# Wall_Crawller_Application.net
KiCad netlist of a schematic drawn in Altium Designer
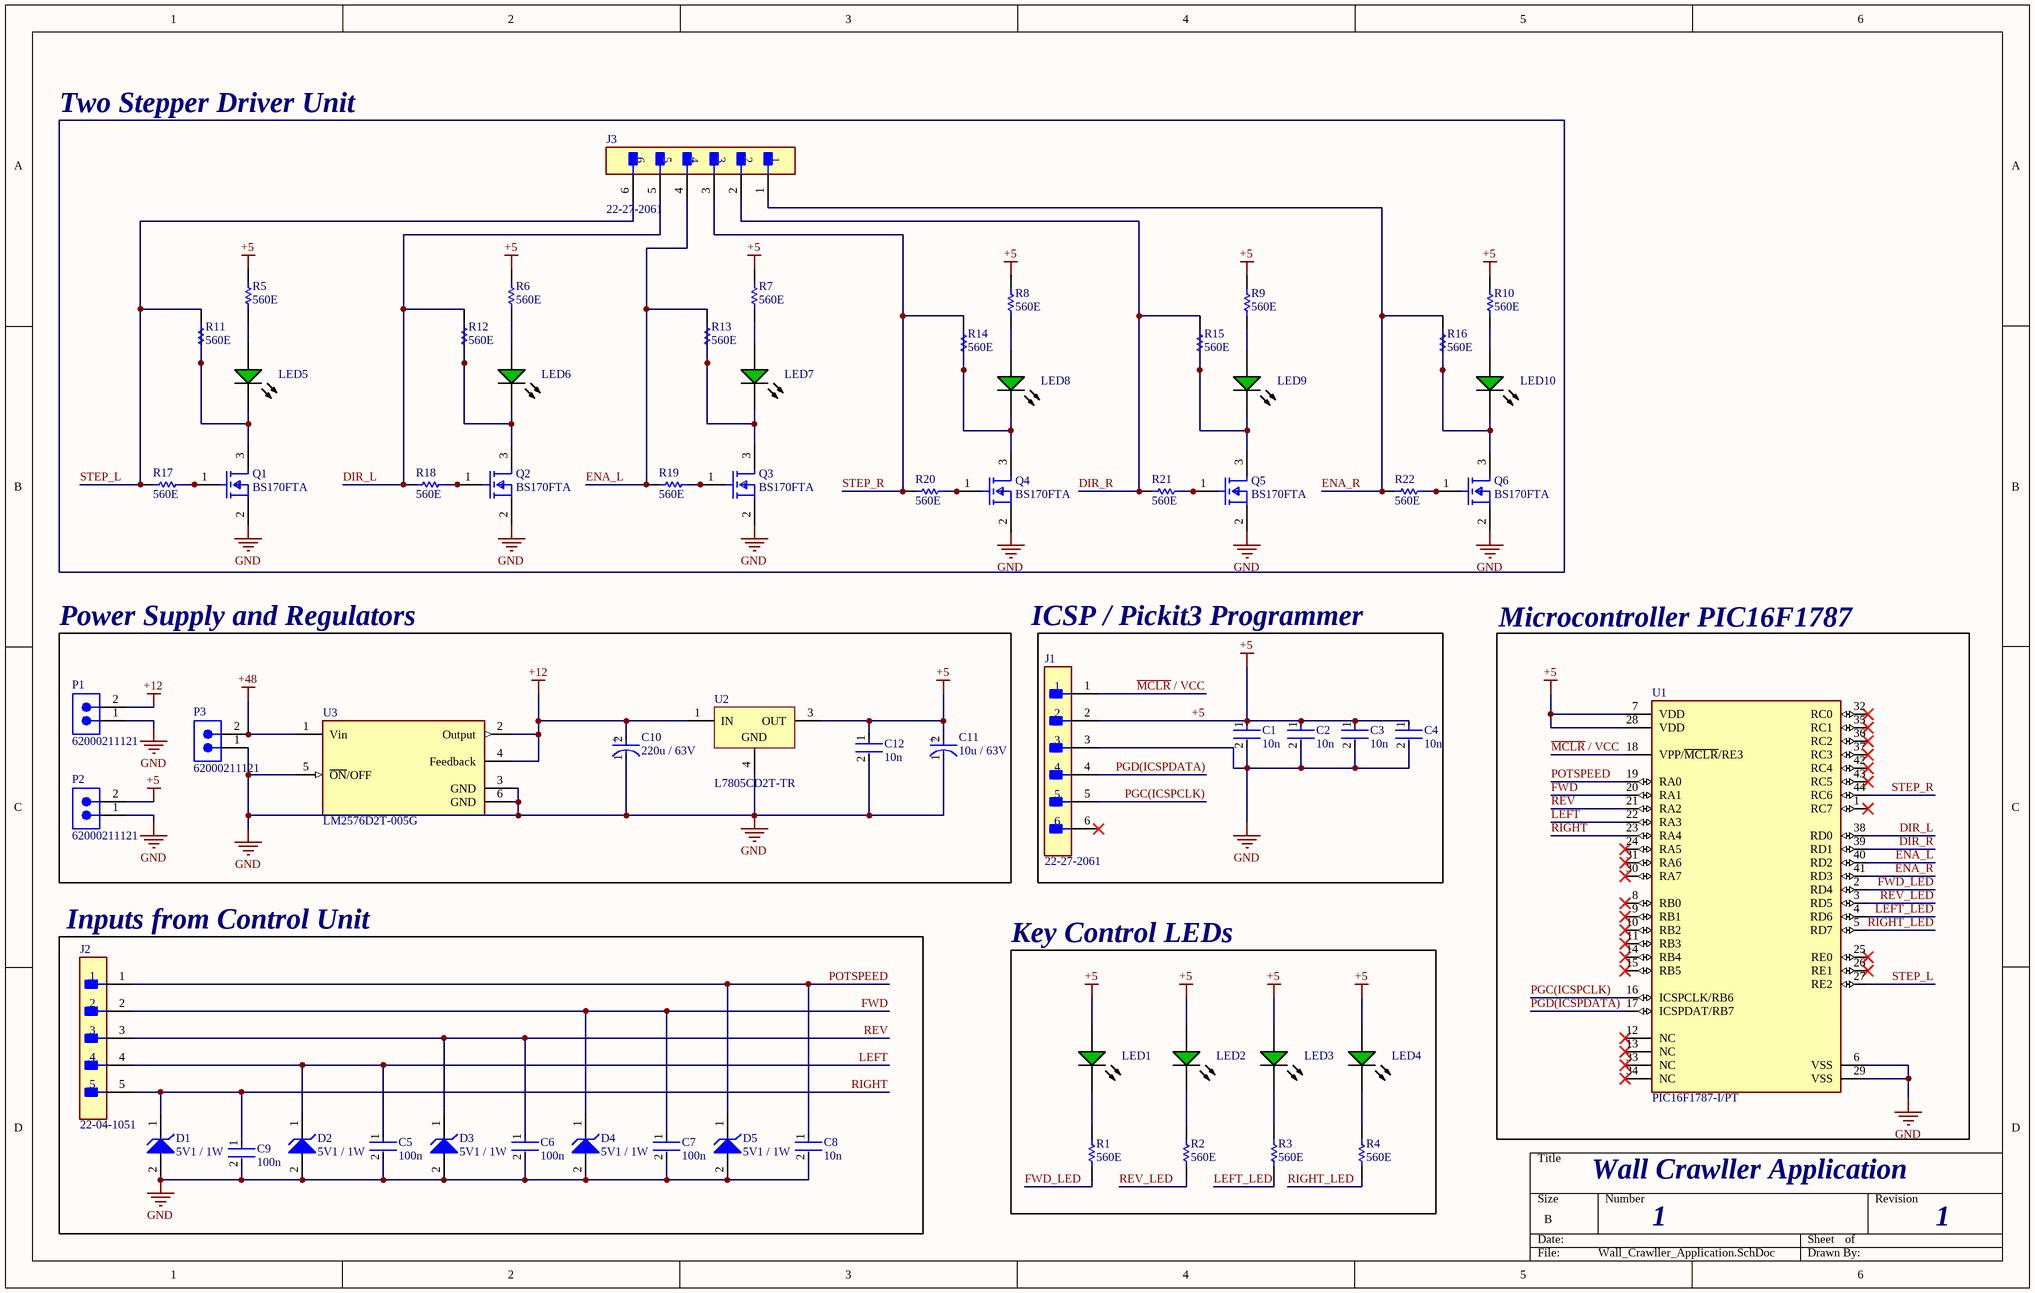
[diagram p0: Wall_Crawller_Application.SchDoc]

(export (version "E")
  (design (tool "Eeschema 10.0.6"))
  (components
    (comp (ref "C1")
      (value "10n")
      (footprint "FP-C0805C-DN-MFG")
      (description "CAP CER 10nF 50V X7R 0805")
      (fields
        (field (name "MANUFACTURER") "KEMET")
        (field (name "OCTOPART") "https://octopart.com/c0805c224k5ractu-kemet-144670")
      )
      (libsource (lib "Altium Content Vault") (part "b4654b650e69147ec39a6b967a45e02"))
    )
    (comp (ref "C2")
      (value "10n")
      (footprint "FP-C0805C-DN-MFG")
      (description "CAP CER 10nF 50V X7R 0805")
      (fields
        (field (name "MANUFACTURER") "KEMET")
        (field (name "OCTOPART") "https://octopart.com/c0805c224k5ractu-kemet-144670")
      )
      (libsource (lib "Altium Content Vault") (part "b4654b650e69147ec39a6b967a45e02"))
    )
    (comp (ref "C3")
      (value "10n")
      (footprint "FP-C0805C-DN-MFG")
      (description "CAP CER 10nF 50V X7R 0805")
      (fields
        (field (name "MANUFACTURER") "KEMET")
        (field (name "OCTOPART") "https://octopart.com/c0805c224k5ractu-kemet-144670")
      )
      (libsource (lib "Altium Content Vault") (part "b4654b650e69147ec39a6b967a45e02"))
    )
    (comp (ref "C4")
      (value "10n")
      (footprint "FP-C0805C-DN-MFG")
      (description "CAP CER 10nF 50V X7R 0805")
      (fields
        (field (name "MANUFACTURER") "KEMET")
        (field (name "OCTOPART") "https://octopart.com/c0805c224k5ractu-kemet-144670")
      )
      (libsource (lib "Altium Content Vault") (part "b4654b650e69147ec39a6b967a45e02"))
    )
    (comp (ref "C5")
      (value "100n")
      (footprint "FP-C0805C-DN-MFG")
      (description "CAP CER 10nF 50V X7R 0805")
      (fields
        (field (name "MANUFACTURER") "KEMET")
        (field (name "OCTOPART") "https://octopart.com/c0805c224k5ractu-kemet-144670")
      )
      (libsource (lib "Altium Content Vault") (part "b4654b650e69147ec39a6b967a45e02"))
    )
    (comp (ref "C6")
      (value "100n")
      (footprint "FP-C0805C-DN-MFG")
      (description "CAP CER 10nF 50V X7R 0805")
      (fields
        (field (name "MANUFACTURER") "KEMET")
        (field (name "OCTOPART") "https://octopart.com/c0805c224k5ractu-kemet-144670")
      )
      (libsource (lib "Altium Content Vault") (part "b4654b650e69147ec39a6b967a45e02"))
    )
    (comp (ref "C7")
      (value "100n")
      (footprint "FP-C0805C-DN-MFG")
      (description "CAP CER 10nF 50V X7R 0805")
      (fields
        (field (name "MANUFACTURER") "KEMET")
        (field (name "OCTOPART") "https://octopart.com/c0805c224k5ractu-kemet-144670")
      )
      (libsource (lib "Altium Content Vault") (part "b4654b650e69147ec39a6b967a45e02"))
    )
    (comp (ref "C8")
      (value "10n")
      (footprint "FP-C0805C-DN-MFG")
      (description "CAP CER 10nF 50V X7R 0805")
      (fields
        (field (name "MANUFACTURER") "KEMET")
        (field (name "OCTOPART") "https://octopart.com/c0805c224k5ractu-kemet-144670")
      )
      (libsource (lib "Altium Content Vault") (part "b4654b650e69147ec39a6b967a45e02"))
    )
    (comp (ref "C9")
      (value "100n")
      (footprint "FP-C0805C-DN-MFG")
      (description "CAP CER 10nF 50V X7R 0805")
      (fields
        (field (name "MANUFACTURER") "KEMET")
        (field (name "OCTOPART") "https://octopart.com/c0805c224k5ractu-kemet-144670")
      )
      (libsource (lib "Altium Content Vault") (part "b4654b650e69147ec39a6b967a45e02"))
    )
    (comp (ref "C10")
      (value "220u / 63V")
      (footprint "FP-T491B107K006AT-MFG")
      (description "CAP TANT 10UF 10% 63V 1411")
      (fields (field (name "VOLTAGE") "6.3V") (field (name "TOLERANCE") "10%"))
      (libsource (lib "Altium Content Vault") (part "a00bbbee19879c290e62620ae7e47b1"))
    )
    (comp (ref "C11")
      (value "10u / 63V")
      (footprint "FP-T491B107K006AT-MFG")
      (description "CAP TANT 10UF 10% 63V 1411")
      (fields (field (name "VOLTAGE") "6.3V") (field (name "TOLERANCE") "10%"))
      (libsource (lib "Altium Content Vault") (part "a00bbbee19879c290e62620ae7e47b1"))
    )
    (comp (ref "C12")
      (value "10n")
      (footprint "FP-C0805C-DN-MFG")
      (description "CAP CER 10nF 50V X7R 0805")
      (fields
        (field (name "MANUFACTURER") "KEMET")
        (field (name "OCTOPART") "https://octopart.com/c0805c224k5ractu-kemet-144670")
      )
      (libsource (lib "Altium Content Vault") (part "b4654b650e69147ec39a6b967a45e02"))
    )
    (comp (ref "D1")
      (value "5V1 / 1W")
      (footprint "ONSC-SOD-123-2-425-04_V")
      (description "Zener Voltage Regulator, 500 mW, 2-Pin SOD-123, Pb-Free, Tape and Reel")
      (fields (field (name "MANUFACTURER") "On Semiconductor") (field (name "PARTNUMBER") "MMSZ4691T1G"))
      (libsource (lib "Altium Content Vault") (part "ONSC-K1A2-2"))
    )
    (comp (ref "D2")
      (value "5V1 / 1W")
      (footprint "ONSC-SOD-123-2-425-04_V")
      (description "Zener Voltage Regulator, 500 mW, 2-Pin SOD-123, Pb-Free, Tape and Reel")
      (fields (field (name "MANUFACTURER") "On Semiconductor") (field (name "PARTNUMBER") "MMSZ4691T1G"))
      (libsource (lib "Altium Content Vault") (part "ONSC-K1A2-2"))
    )
    (comp (ref "D3")
      (value "5V1 / 1W")
      (footprint "ONSC-SOD-123-2-425-04_V")
      (description "Zener Voltage Regulator, 500 mW, 2-Pin SOD-123, Pb-Free, Tape and Reel")
      (fields (field (name "MANUFACTURER") "On Semiconductor") (field (name "PARTNUMBER") "MMSZ4691T1G"))
      (libsource (lib "Altium Content Vault") (part "ONSC-K1A2-2"))
    )
    (comp (ref "D4")
      (value "5V1 / 1W")
      (footprint "ONSC-SOD-123-2-425-04_V")
      (description "Zener Voltage Regulator, 500 mW, 2-Pin SOD-123, Pb-Free, Tape and Reel")
      (fields (field (name "MANUFACTURER") "On Semiconductor") (field (name "PARTNUMBER") "MMSZ4691T1G"))
      (libsource (lib "Altium Content Vault") (part "ONSC-K1A2-2"))
    )
    (comp (ref "D5")
      (value "5V1 / 1W")
      (footprint "ONSC-SOD-123-2-425-04_V")
      (description "Zener Voltage Regulator, 500 mW, 2-Pin SOD-123, Pb-Free, Tape and Reel")
      (fields (field (name "MANUFACTURER") "On Semiconductor") (field (name "PARTNUMBER") "MMSZ4691T1G"))
      (libsource (lib "Altium Content Vault") (part "ONSC-K1A2-2"))
    )
    (comp (ref "J1")
      (value "22-27-2061")
      (footprint "FP-22-27-2061-MFG")
      (description "CONN HEADER VERT 6POS 2.54MM")
      (libsource (lib "Altium Content Vault") (part "f2cb566baf1c37ab5a3b8e90bbeafd6"))
    )
    (comp (ref "J2")
      (value "22-04-1051")
      (footprint "FP-22-04-1051-MFG")
      (description "22-04-1051 KK Mini-Latch Straight Male, PCB Header, Through Hole, 1 Rows, 5 Contacts, 2.5mm Pitch")
      (libsource (lib "Altium Content Vault") (part "bf93c07fd2649a848d0ec8585582aab"))
    )
    (comp (ref "J3")
      (value "22-27-2061")
      (footprint "FP-22-27-2061-MFG")
      (description "CONN HEADER VERT 6POS 2.54MM")
      (libsource (lib "") (part "f2cb566baf1c37ab5a3b8e90bbeafd6_1"))
    )
    (comp (ref "LED1")
      (value "~")
      (footprint "AVAG-HSMX-C170_V")
      (description "Chip LED, Green, 2.2 V, -40 to 85 degC, 2-Pin SMD, Pb-Free, Tape and Reel")
      (fields (field (name "MANUFACTURER") "Avago"))
      (libsource (lib "Altium Content Vault") (part "LED_GREEN_A1K2-2"))
    )
    (comp (ref "LED2")
      (value "~")
      (footprint "AVAG-HSMX-C170_V")
      (description "Chip LED, Green, 2.2 V, -40 to 85 degC, 2-Pin SMD, Pb-Free, Tape and Reel")
      (fields (field (name "MANUFACTURER") "Avago"))
      (libsource (lib "Altium Content Vault") (part "LED_GREEN_A1K2-2"))
    )
    (comp (ref "LED3")
      (value "~")
      (footprint "AVAG-HSMX-C170_V")
      (description "Chip LED, Green, 2.2 V, -40 to 85 degC, 2-Pin SMD, Pb-Free, Tape and Reel")
      (fields (field (name "MANUFACTURER") "Avago"))
      (libsource (lib "Altium Content Vault") (part "LED_GREEN_A1K2-2"))
    )
    (comp (ref "LED4")
      (value "~")
      (footprint "AVAG-HSMX-C170_V")
      (description "Chip LED, Green, 2.2 V, -40 to 85 degC, 2-Pin SMD, Pb-Free, Tape and Reel")
      (fields (field (name "MANUFACTURER") "Avago"))
      (libsource (lib "Altium Content Vault") (part "LED_GREEN_A1K2-2"))
    )
    (comp (ref "LED5")
      (value "~")
      (footprint "AVAG-HSMX-C170_V")
      (description "Chip LED, Green, 2.2 V, -40 to 85 degC, 2-Pin SMD, Pb-Free, Tape and Reel")
      (fields (field (name "MANUFACTURER") "Avago"))
      (libsource (lib "Altium Content Vault") (part "LED_GREEN_A1K2-2"))
    )
    (comp (ref "LED6")
      (value "~")
      (footprint "AVAG-HSMX-C170_V")
      (description "Chip LED, Green, 2.2 V, -40 to 85 degC, 2-Pin SMD, Pb-Free, Tape and Reel")
      (fields (field (name "MANUFACTURER") "Avago"))
      (libsource (lib "Altium Content Vault") (part "LED_GREEN_A1K2-2"))
    )
    (comp (ref "LED7")
      (value "~")
      (footprint "AVAG-HSMX-C170_V")
      (description "Chip LED, Green, 2.2 V, -40 to 85 degC, 2-Pin SMD, Pb-Free, Tape and Reel")
      (fields (field (name "MANUFACTURER") "Avago"))
      (libsource (lib "Altium Content Vault") (part "LED_GREEN_A1K2-2"))
    )
    (comp (ref "LED8")
      (value "~")
      (footprint "AVAG-HSMX-C170_V")
      (description "Chip LED, Green, 2.2 V, -40 to 85 degC, 2-Pin SMD, Pb-Free, Tape and Reel")
      (fields (field (name "MANUFACTURER") "Avago"))
      (libsource (lib "Altium Content Vault") (part "LED_GREEN_A1K2-2"))
    )
    (comp (ref "LED9")
      (value "~")
      (footprint "AVAG-HSMX-C170_V")
      (description "Chip LED, Green, 2.2 V, -40 to 85 degC, 2-Pin SMD, Pb-Free, Tape and Reel")
      (fields (field (name "MANUFACTURER") "Avago"))
      (libsource (lib "Altium Content Vault") (part "LED_GREEN_A1K2-2"))
    )
    (comp (ref "LED10")
      (value "~")
      (footprint "AVAG-HSMX-C170_V")
      (description "Chip LED, Green, 2.2 V, -40 to 85 degC, 2-Pin SMD, Pb-Free, Tape and Reel")
      (fields (field (name "MANUFACTURER") "Avago"))
      (libsource (lib "Altium Content Vault") (part "LED_GREEN_A1K2-2"))
    )
    (comp (ref "P1")
      (value "62000211121")
      (footprint "62000211121")
      (libsource (lib "Altium Content Vault") (part "Header_Male_1R_02P"))
    )
    (comp (ref "P2")
      (value "62000211121")
      (footprint "62000211121")
      (libsource (lib "Altium Content Vault") (part "Header_Male_1R_02P"))
    )
    (comp (ref "P3")
      (value "62000211121")
      (footprint "62000211121")
      (libsource (lib "Altium Content Vault") (part "Header_Male_1R_02P"))
    )
    (comp (ref "Q1")
      (value "BS170FTA")
      (footprint "FP-SOT23-IPC_A")
      (description "MOSFET N-CH 60V .15MA SOT23-3")
      (libsource (lib "Altium Content Vault") (part "922b338f6e3d8e31c27d5626d96ce2a"))
    )
    (comp (ref "Q2")
      (value "BS170FTA")
      (footprint "FP-SOT23-IPC_A")
      (description "MOSFET N-CH 60V .15MA SOT23-3")
      (libsource (lib "Altium Content Vault") (part "922b338f6e3d8e31c27d5626d96ce2a"))
    )
    (comp (ref "Q3")
      (value "BS170FTA")
      (footprint "FP-SOT23-IPC_A")
      (description "MOSFET N-CH 60V .15MA SOT23-3")
      (libsource (lib "Altium Content Vault") (part "922b338f6e3d8e31c27d5626d96ce2a"))
    )
    (comp (ref "Q4")
      (value "BS170FTA")
      (footprint "FP-SOT23-IPC_A")
      (description "MOSFET N-CH 60V .15MA SOT23-3")
      (libsource (lib "Altium Content Vault") (part "922b338f6e3d8e31c27d5626d96ce2a"))
    )
    (comp (ref "Q5")
      (value "BS170FTA")
      (footprint "FP-SOT23-IPC_A")
      (description "MOSFET N-CH 60V .15MA SOT23-3")
      (libsource (lib "Altium Content Vault") (part "922b338f6e3d8e31c27d5626d96ce2a"))
    )
    (comp (ref "Q6")
      (value "BS170FTA")
      (footprint "FP-SOT23-IPC_A")
      (description "MOSFET N-CH 60V .15MA SOT23-3")
      (libsource (lib "Altium Content Vault") (part "922b338f6e3d8e31c27d5626d96ce2a"))
    )
    (comp (ref "R1")
      (value "560E")
      (footprint "RESC2013X50X30LL20T20")
      (fields (field (name "MANUFACTURER") "Vishay Dale") (field (name "PART NUMBER") "CRCW08050000Z0EA"))
      (libsource (lib "Altium Content Vault") (part "RES"))
    )
    (comp (ref "R2")
      (value "560E")
      (footprint "RESC2013X50X30LL20T20")
      (fields (field (name "MANUFACTURER") "Vishay Dale") (field (name "PART NUMBER") "CRCW08050000Z0EA"))
      (libsource (lib "Altium Content Vault") (part "RES"))
    )
    (comp (ref "R3")
      (value "560E")
      (footprint "RESC2013X50X30LL20T20")
      (fields (field (name "MANUFACTURER") "Vishay Dale") (field (name "PART NUMBER") "CRCW08050000Z0EA"))
      (libsource (lib "Altium Content Vault") (part "RES"))
    )
    (comp (ref "R4")
      (value "560E")
      (footprint "RESC2013X50X30LL20T20")
      (fields (field (name "MANUFACTURER") "Vishay Dale") (field (name "PART NUMBER") "CRCW08050000Z0EA"))
      (libsource (lib "Altium Content Vault") (part "RES"))
    )
    (comp (ref "R5")
      (value "560E")
      (footprint "RESC2013X50X30LL20T20")
      (fields (field (name "MANUFACTURER") "Vishay Dale") (field (name "PART NUMBER") "CRCW08050000Z0EA"))
      (libsource (lib "Altium Content Vault") (part "RES"))
    )
    (comp (ref "R6")
      (value "560E")
      (footprint "RESC2013X50X30LL20T20")
      (fields (field (name "MANUFACTURER") "Vishay Dale") (field (name "PART NUMBER") "CRCW08050000Z0EA"))
      (libsource (lib "Altium Content Vault") (part "RES"))
    )
    (comp (ref "R7")
      (value "560E")
      (footprint "RESC2013X50X30LL20T20")
      (fields (field (name "MANUFACTURER") "Vishay Dale") (field (name "PART NUMBER") "CRCW08050000Z0EA"))
      (libsource (lib "Altium Content Vault") (part "RES"))
    )
    (comp (ref "R8")
      (value "560E")
      (footprint "RESC2013X50X30LL20T20")
      (fields (field (name "MANUFACTURER") "Vishay Dale") (field (name "PART NUMBER") "CRCW08050000Z0EA"))
      (libsource (lib "Altium Content Vault") (part "RES"))
    )
    (comp (ref "R9")
      (value "560E")
      (footprint "RESC2013X50X30LL20T20")
      (fields (field (name "MANUFACTURER") "Vishay Dale") (field (name "PART NUMBER") "CRCW08050000Z0EA"))
      (libsource (lib "Altium Content Vault") (part "RES"))
    )
    (comp (ref "R10")
      (value "560E")
      (footprint "RESC2013X50X30LL20T20")
      (fields (field (name "MANUFACTURER") "Vishay Dale") (field (name "PART NUMBER") "CRCW08050000Z0EA"))
      (libsource (lib "Altium Content Vault") (part "RES"))
    )
    (comp (ref "R11")
      (value "560E")
      (footprint "RESC2013X50X30LL20T20")
      (fields (field (name "MANUFACTURER") "Vishay Dale") (field (name "PART NUMBER") "CRCW08050000Z0EA"))
      (libsource (lib "Altium Content Vault") (part "RES"))
    )
    (comp (ref "R12")
      (value "560E")
      (footprint "RESC2013X50X30LL20T20")
      (fields (field (name "MANUFACTURER") "Vishay Dale") (field (name "PART NUMBER") "CRCW08050000Z0EA"))
      (libsource (lib "Altium Content Vault") (part "RES"))
    )
    (comp (ref "R13")
      (value "560E")
      (footprint "RESC2013X50X30LL20T20")
      (fields (field (name "MANUFACTURER") "Vishay Dale") (field (name "PART NUMBER") "CRCW08050000Z0EA"))
      (libsource (lib "Altium Content Vault") (part "RES"))
    )
    (comp (ref "R14")
      (value "560E")
      (footprint "RESC2013X50X30LL20T20")
      (fields (field (name "MANUFACTURER") "Vishay Dale") (field (name "PART NUMBER") "CRCW08050000Z0EA"))
      (libsource (lib "Altium Content Vault") (part "RES"))
    )
    (comp (ref "R15")
      (value "560E")
      (footprint "RESC2013X50X30LL20T20")
      (fields (field (name "MANUFACTURER") "Vishay Dale") (field (name "PART NUMBER") "CRCW08050000Z0EA"))
      (libsource (lib "Altium Content Vault") (part "RES"))
    )
    (comp (ref "R16")
      (value "560E")
      (footprint "RESC2013X50X30LL20T20")
      (fields (field (name "MANUFACTURER") "Vishay Dale") (field (name "PART NUMBER") "CRCW08050000Z0EA"))
      (libsource (lib "Altium Content Vault") (part "RES"))
    )
    (comp (ref "R17")
      (value "560E")
      (footprint "RESC2013X50X30LL20T20")
      (fields (field (name "MANUFACTURER") "Vishay Dale") (field (name "PART NUMBER") "CRCW08050000Z0EA"))
      (libsource (lib "Altium Content Vault") (part "RES"))
    )
    (comp (ref "R18")
      (value "560E")
      (footprint "RESC2013X50X30LL20T20")
      (fields (field (name "MANUFACTURER") "Vishay Dale") (field (name "PART NUMBER") "CRCW08050000Z0EA"))
      (libsource (lib "Altium Content Vault") (part "RES"))
    )
    (comp (ref "R19")
      (value "560E")
      (footprint "RESC2013X50X30LL20T20")
      (fields (field (name "MANUFACTURER") "Vishay Dale") (field (name "PART NUMBER") "CRCW08050000Z0EA"))
      (libsource (lib "Altium Content Vault") (part "RES"))
    )
    (comp (ref "R20")
      (value "560E")
      (footprint "RESC2013X50X30LL20T20")
      (fields (field (name "MANUFACTURER") "Vishay Dale") (field (name "PART NUMBER") "CRCW08050000Z0EA"))
      (libsource (lib "Altium Content Vault") (part "RES"))
    )
    (comp (ref "R21")
      (value "560E")
      (footprint "RESC2013X50X30LL20T20")
      (fields (field (name "MANUFACTURER") "Vishay Dale") (field (name "PART NUMBER") "CRCW08050000Z0EA"))
      (libsource (lib "Altium Content Vault") (part "RES"))
    )
    (comp (ref "R22")
      (value "560E")
      (footprint "RESC2013X50X30LL20T20")
      (fields (field (name "MANUFACTURER") "Vishay Dale") (field (name "PART NUMBER") "CRCW08050000Z0EA"))
      (libsource (lib "Altium Content Vault") (part "RES"))
    )
    (comp (ref "U1")
      (value "PIC16F1787-I/PT")
      (footprint "FP-C04-076-IPC_A")
      (description "IC MCU 8BIT 14KB FLASH 44TQFP")
      (libsource (lib "Altium Content Vault") (part "e6b7bcb1559260578a3a8e1800748af"))
    )
    (comp (ref "U2")
      (value "L7805CD2T-TR")
      (footprint "TO-263_M")
      (description "Positive Voltage Regulator, 3-Pin D2PAK, Tape and Reel")
      (libsource (lib "Altium Content Vault") (part "PM-REG-L4940-SOT3"))
    )
    (comp (ref "U3")
      (value "LM2576D2T-005G")
      (footprint "FP-936A-02-MFG")
      (description "IC REG MULTI CONFG 5V 3A D2PAK-5")
      (fields
        (field (name "MANUFACTURER") "ON Semiconductor")
        (field (name "OCTOPART") "https://octopart.com/lm2576d2t-005g-on+semiconductor-725168")
      )
      (libsource (lib "Altium Content Vault") (part "c423ec427ffa15a9162ce552835b611"))
    )
  )
  (nets
    (net (code "1") (name "+5") (class "Default")
      (node (ref "C1") (pin "1") (pinfunction "1_1") (pintype "passive"))
      (node (ref "C11") (pin "2") (pinfunction "A_2") (pintype "passive"))
      (node (ref "C12") (pin "1") (pinfunction "1_1") (pintype "passive"))
      (node (ref "C2") (pin "1") (pinfunction "1_1") (pintype "passive"))
      (node (ref "C3") (pin "1") (pinfunction "1_1") (pintype "passive"))
      (node (ref "C4") (pin "1") (pinfunction "1_1") (pintype "passive"))
      (node (ref "J1") (pin "2") (pinfunction "2_2") (pintype "passive"))
      (node (ref "LED1") (pin "1") (pinfunction "A_1") (pintype "passive"))
      (node (ref "LED2") (pin "1") (pinfunction "A_1") (pintype "passive"))
      (node (ref "LED3") (pin "1") (pinfunction "A_1") (pintype "passive"))
      (node (ref "LED4") (pin "1") (pinfunction "A_1") (pintype "passive"))
      (node (ref "P2") (pin "2") (pinfunction "2_2") (pintype "passive"))
      (node (ref "R10") (pin "2") (pinfunction "2_2") (pintype "passive"))
      (node (ref "R5") (pin "2") (pinfunction "2_2") (pintype "passive"))
      (node (ref "R6") (pin "2") (pinfunction "2_2") (pintype "passive"))
      (node (ref "R7") (pin "2") (pinfunction "2_2") (pintype "passive"))
      (node (ref "R8") (pin "2") (pinfunction "2_2") (pintype "passive"))
      (node (ref "R9") (pin "2") (pinfunction "2_2") (pintype "passive"))
      (node (ref "U1") (pin "28") (pinfunction "VDD_28") (pintype "power_in"))
      (node (ref "U1") (pin "7") (pinfunction "VDD_7") (pintype "power_in"))
      (node (ref "U2") (pin "3") (pinfunction "OUT_3") (pintype "power_in"))
    )
    (net (code "2") (name "+12") (class "Default")
      (node (ref "C10") (pin "2") (pinfunction "A_2") (pintype "passive"))
      (node (ref "P1") (pin "2") (pinfunction "2_2") (pintype "passive"))
      (node (ref "U2") (pin "1") (pinfunction "IN_1") (pintype "power_in"))
      (node (ref "U3") (pin "2") (pinfunction "Output_2") (pintype "output"))
      (node (ref "U3") (pin "4") (pinfunction "Feedback_4") (pintype "passive"))
    )
    (net (code "3") (name "+48") (class "Default")
      (node (ref "P3") (pin "2") (pinfunction "2_2") (pintype "passive"))
      (node (ref "U3") (pin "1") (pinfunction "Vin_1") (pintype "power_in"))
    )
    (net (code "4") (name "/DIR_L") (class "Default")
      (node (ref "J3") (pin "5") (pinfunction "5_5") (pintype "passive"))
      (node (ref "R12") (pin "2") (pinfunction "2_2") (pintype "passive"))
      (node (ref "R18") (pin "2") (pinfunction "2_2") (pintype "passive"))
      (node (ref "U1") (pin "38") (pinfunction "RD0_38") (pintype "bidirectional"))
    )
    (net (code "5") (name "/DIR_R") (class "Default")
      (node (ref "J3") (pin "2") (pinfunction "2_2") (pintype "passive"))
      (node (ref "R15") (pin "2") (pinfunction "2_2") (pintype "passive"))
      (node (ref "R21") (pin "2") (pinfunction "2_2") (pintype "passive"))
      (node (ref "U1") (pin "39") (pinfunction "RD1_39") (pintype "bidirectional"))
    )
    (net (code "6") (name "/ENA_L") (class "Default")
      (node (ref "J3") (pin "4") (pinfunction "4_4") (pintype "passive"))
      (node (ref "R13") (pin "2") (pinfunction "2_2") (pintype "passive"))
      (node (ref "R19") (pin "2") (pinfunction "2_2") (pintype "passive"))
      (node (ref "U1") (pin "40") (pinfunction "RD2_40") (pintype "bidirectional"))
    )
    (net (code "7") (name "/ENA_R") (class "Default")
      (node (ref "J3") (pin "1") (pinfunction "1_1") (pintype "passive"))
      (node (ref "R16") (pin "2") (pinfunction "2_2") (pintype "passive"))
      (node (ref "R22") (pin "2") (pinfunction "2_2") (pintype "passive"))
      (node (ref "U1") (pin "41") (pinfunction "RD3_41") (pintype "bidirectional"))
    )
    (net (code "8") (name "/FWD") (class "Default")
      (node (ref "C7") (pin "1") (pinfunction "1_1") (pintype "passive"))
      (node (ref "D4") (pin "1") (pinfunction "K_1") (pintype "passive"))
      (node (ref "J2") (pin "2") (pinfunction "2_2") (pintype "passive"))
      (node (ref "U1") (pin "20") (pinfunction "RA1_20") (pintype "bidirectional"))
    )
    (net (code "9") (name "/FWD_LED") (class "Default")
      (node (ref "R1") (pin "1") (pinfunction "1_1") (pintype "passive"))
      (node (ref "U1") (pin "2") (pinfunction "RD4_2") (pintype "bidirectional"))
    )
    (net (code "10") (name "/LEFT") (class "Default")
      (node (ref "C5") (pin "1") (pinfunction "1_1") (pintype "passive"))
      (node (ref "D2") (pin "1") (pinfunction "K_1") (pintype "passive"))
      (node (ref "J2") (pin "4") (pinfunction "4_4") (pintype "passive"))
      (node (ref "U1") (pin "22") (pinfunction "RA3_22") (pintype "bidirectional"))
    )
    (net (code "11") (name "/LEFT_LED") (class "Default")
      (node (ref "R3") (pin "1") (pinfunction "1_1") (pintype "passive"))
      (node (ref "U1") (pin "4") (pinfunction "RD6_4") (pintype "bidirectional"))
    )
    (net (code "12") (name "/PGC(ICSPCLK)") (class "Default")
      (node (ref "J1") (pin "5") (pinfunction "5_5") (pintype "passive"))
      (node (ref "U1") (pin "16") (pinfunction "ICSPCLK/RB6_16") (pintype "bidirectional"))
    )
    (net (code "13") (name "/PGD(ICSPDATA)") (class "Default")
      (node (ref "J1") (pin "4") (pinfunction "4_4") (pintype "passive"))
      (node (ref "U1") (pin "17") (pinfunction "ICSPDAT/RB7_17") (pintype "bidirectional"))
    )
    (net (code "14") (name "/POTSPEED") (class "Default")
      (node (ref "C8") (pin "1") (pinfunction "1_1") (pintype "passive"))
      (node (ref "D5") (pin "1") (pinfunction "K_1") (pintype "passive"))
      (node (ref "J2") (pin "1") (pinfunction "1_1") (pintype "passive"))
      (node (ref "U1") (pin "19") (pinfunction "RA0_19") (pintype "bidirectional"))
    )
    (net (code "15") (name "/REV") (class "Default")
      (node (ref "C6") (pin "1") (pinfunction "1_1") (pintype "passive"))
      (node (ref "D3") (pin "1") (pinfunction "K_1") (pintype "passive"))
      (node (ref "J2") (pin "3") (pinfunction "3_3") (pintype "passive"))
      (node (ref "U1") (pin "21") (pinfunction "RA2_21") (pintype "bidirectional"))
    )
    (net (code "16") (name "/REV_LED") (class "Default")
      (node (ref "R2") (pin "1") (pinfunction "1_1") (pintype "passive"))
      (node (ref "U1") (pin "3") (pinfunction "RD5_3") (pintype "bidirectional"))
    )
    (net (code "17") (name "/RIGHT") (class "Default")
      (node (ref "C9") (pin "1") (pinfunction "1_1") (pintype "passive"))
      (node (ref "D1") (pin "1") (pinfunction "K_1") (pintype "passive"))
      (node (ref "J2") (pin "5") (pinfunction "5_5") (pintype "passive"))
      (node (ref "U1") (pin "23") (pinfunction "RA4_23") (pintype "bidirectional"))
    )
    (net (code "18") (name "/RIGHT_LED") (class "Default")
      (node (ref "R4") (pin "1") (pinfunction "1_1") (pintype "passive"))
      (node (ref "U1") (pin "5") (pinfunction "RD7_5") (pintype "bidirectional"))
    )
    (net (code "19") (name "/STEP_L") (class "Default")
      (node (ref "J3") (pin "6") (pinfunction "6_6") (pintype "passive"))
      (node (ref "R11") (pin "2") (pinfunction "2_2") (pintype "passive"))
      (node (ref "R17") (pin "2") (pinfunction "2_2") (pintype "passive"))
      (node (ref "U1") (pin "27") (pinfunction "RE2_27") (pintype "bidirectional"))
    )
    (net (code "20") (name "/STEP_R") (class "Default")
      (node (ref "J3") (pin "3") (pinfunction "3_3") (pintype "passive"))
      (node (ref "R14") (pin "2") (pinfunction "2_2") (pintype "passive"))
      (node (ref "R20") (pin "2") (pinfunction "2_2") (pintype "passive"))
      (node (ref "U1") (pin "44") (pinfunction "RC6_44") (pintype "bidirectional"))
    )
    (net (code "21") (name "/~{MCLR} {slash} VCC") (class "Default")
      (node (ref "J1") (pin "1") (pinfunction "1_1") (pintype "passive"))
      (node (ref "U1") (pin "18") (pinfunction "VPP/~{MCLR}/RE3_18") (pintype "passive"))
    )
    (net (code "22") (name "GND") (class "Default")
      (node (ref "C1") (pin "2") (pinfunction "2_2") (pintype "passive"))
      (node (ref "C10") (pin "1") (pinfunction "C_1") (pintype "passive"))
      (node (ref "C11") (pin "1") (pinfunction "C_1") (pintype "passive"))
      (node (ref "C12") (pin "2") (pinfunction "2_2") (pintype "passive"))
      (node (ref "C2") (pin "2") (pinfunction "2_2") (pintype "passive"))
      (node (ref "C3") (pin "2") (pinfunction "2_2") (pintype "passive"))
      (node (ref "C4") (pin "2") (pinfunction "2_2") (pintype "passive"))
      (node (ref "C5") (pin "2") (pinfunction "2_2") (pintype "passive"))
      (node (ref "C6") (pin "2") (pinfunction "2_2") (pintype "passive"))
      (node (ref "C7") (pin "2") (pinfunction "2_2") (pintype "passive"))
      (node (ref "C8") (pin "2") (pinfunction "2_2") (pintype "passive"))
      (node (ref "C9") (pin "2") (pinfunction "2_2") (pintype "passive"))
      (node (ref "D1") (pin "2") (pinfunction "A_2") (pintype "passive"))
      (node (ref "D2") (pin "2") (pinfunction "A_2") (pintype "passive"))
      (node (ref "D3") (pin "2") (pinfunction "A_2") (pintype "passive"))
      (node (ref "D4") (pin "2") (pinfunction "A_2") (pintype "passive"))
      (node (ref "D5") (pin "2") (pinfunction "A_2") (pintype "passive"))
      (node (ref "J1") (pin "3") (pinfunction "3_3") (pintype "passive"))
      (node (ref "P1") (pin "1") (pinfunction "1_1") (pintype "passive"))
      (node (ref "P2") (pin "1") (pinfunction "1_1") (pintype "passive"))
      (node (ref "P3") (pin "1") (pinfunction "1_1") (pintype "passive"))
      (node (ref "Q1") (pin "2") (pinfunction "S_2") (pintype "passive"))
      (node (ref "Q2") (pin "2") (pinfunction "S_2") (pintype "passive"))
      (node (ref "Q3") (pin "2") (pinfunction "S_2") (pintype "passive"))
      (node (ref "Q4") (pin "2") (pinfunction "S_2") (pintype "passive"))
      (node (ref "Q5") (pin "2") (pinfunction "S_2") (pintype "passive"))
      (node (ref "Q6") (pin "2") (pinfunction "S_2") (pintype "passive"))
      (node (ref "U1") (pin "29") (pinfunction "VSS_29") (pintype "passive"))
      (node (ref "U1") (pin "6") (pinfunction "VSS_6") (pintype "passive"))
      (node (ref "U2") (pin "4") (pinfunction "GND_4") (pintype "power_in"))
      (node (ref "U3") (pin "3") (pinfunction "GND_3") (pintype "power_in"))
      (node (ref "U3") (pin "5") (pinfunction "~{ON}/OFF_5") (pintype "input"))
      (node (ref "U3") (pin "6") (pinfunction "GND_6") (pintype "power_in"))
    )
    (net (code "23") (name "Net-(LED1-K)") (class "Default")
      (node (ref "LED1") (pin "2") (pinfunction "K_2") (pintype "passive"))
      (node (ref "R1") (pin "2") (pinfunction "2_2") (pintype "passive"))
    )
    (net (code "24") (name "Net-(LED2-K)") (class "Default")
      (node (ref "LED2") (pin "2") (pinfunction "K_2") (pintype "passive"))
      (node (ref "R2") (pin "2") (pinfunction "2_2") (pintype "passive"))
    )
    (net (code "25") (name "Net-(LED3-K)") (class "Default")
      (node (ref "LED3") (pin "2") (pinfunction "K_2") (pintype "passive"))
      (node (ref "R3") (pin "2") (pinfunction "2_2") (pintype "passive"))
    )
    (net (code "26") (name "Net-(LED4-K)") (class "Default")
      (node (ref "LED4") (pin "2") (pinfunction "K_2") (pintype "passive"))
      (node (ref "R4") (pin "2") (pinfunction "2_2") (pintype "passive"))
    )
    (net (code "27") (name "Net-(LED5-A)") (class "Default")
      (node (ref "LED5") (pin "1") (pinfunction "A_1") (pintype "passive"))
      (node (ref "R5") (pin "1") (pinfunction "1_1") (pintype "passive"))
    )
    (net (code "28") (name "Net-(LED5-K)") (class "Default")
      (node (ref "LED5") (pin "2") (pinfunction "K_2") (pintype "passive"))
      (node (ref "Q1") (pin "3") (pinfunction "D_3") (pintype "passive"))
      (node (ref "R11") (pin "1") (pinfunction "1_1") (pintype "passive"))
    )
    (net (code "29") (name "Net-(LED6-A)") (class "Default")
      (node (ref "LED6") (pin "1") (pinfunction "A_1") (pintype "passive"))
      (node (ref "R6") (pin "1") (pinfunction "1_1") (pintype "passive"))
    )
    (net (code "30") (name "Net-(LED6-K)") (class "Default")
      (node (ref "LED6") (pin "2") (pinfunction "K_2") (pintype "passive"))
      (node (ref "Q2") (pin "3") (pinfunction "D_3") (pintype "passive"))
      (node (ref "R12") (pin "1") (pinfunction "1_1") (pintype "passive"))
    )
    (net (code "31") (name "Net-(LED7-A)") (class "Default")
      (node (ref "LED7") (pin "1") (pinfunction "A_1") (pintype "passive"))
      (node (ref "R7") (pin "1") (pinfunction "1_1") (pintype "passive"))
    )
    (net (code "32") (name "Net-(LED7-K)") (class "Default")
      (node (ref "LED7") (pin "2") (pinfunction "K_2") (pintype "passive"))
      (node (ref "Q3") (pin "3") (pinfunction "D_3") (pintype "passive"))
      (node (ref "R13") (pin "1") (pinfunction "1_1") (pintype "passive"))
    )
    (net (code "33") (name "Net-(LED8-A)") (class "Default")
      (node (ref "LED8") (pin "1") (pinfunction "A_1") (pintype "passive"))
      (node (ref "R8") (pin "1") (pinfunction "1_1") (pintype "passive"))
    )
    (net (code "34") (name "Net-(LED8-K)") (class "Default")
      (node (ref "LED8") (pin "2") (pinfunction "K_2") (pintype "passive"))
      (node (ref "Q4") (pin "3") (pinfunction "D_3") (pintype "passive"))
      (node (ref "R14") (pin "1") (pinfunction "1_1") (pintype "passive"))
    )
    (net (code "35") (name "Net-(LED9-A)") (class "Default")
      (node (ref "LED9") (pin "1") (pinfunction "A_1") (pintype "passive"))
      (node (ref "R9") (pin "1") (pinfunction "1_1") (pintype "passive"))
    )
    (net (code "36") (name "Net-(LED9-K)") (class "Default")
      (node (ref "LED9") (pin "2") (pinfunction "K_2") (pintype "passive"))
      (node (ref "Q5") (pin "3") (pinfunction "D_3") (pintype "passive"))
      (node (ref "R15") (pin "1") (pinfunction "1_1") (pintype "passive"))
    )
    (net (code "37") (name "Net-(LED10-A)") (class "Default")
      (node (ref "LED10") (pin "1") (pinfunction "A_1") (pintype "passive"))
      (node (ref "R10") (pin "1") (pinfunction "1_1") (pintype "passive"))
    )
    (net (code "38") (name "Net-(LED10-K)") (class "Default")
      (node (ref "LED10") (pin "2") (pinfunction "K_2") (pintype "passive"))
      (node (ref "Q6") (pin "3") (pinfunction "D_3") (pintype "passive"))
      (node (ref "R16") (pin "1") (pinfunction "1_1") (pintype "passive"))
    )
    (net (code "39") (name "Net-(Q1-G)") (class "Default")
      (node (ref "Q1") (pin "1") (pinfunction "G_1") (pintype "passive"))
      (node (ref "R17") (pin "1") (pinfunction "1_1") (pintype "passive"))
    )
    (net (code "40") (name "Net-(Q2-G)") (class "Default")
      (node (ref "Q2") (pin "1") (pinfunction "G_1") (pintype "passive"))
      (node (ref "R18") (pin "1") (pinfunction "1_1") (pintype "passive"))
    )
    (net (code "41") (name "Net-(Q3-G)") (class "Default")
      (node (ref "Q3") (pin "1") (pinfunction "G_1") (pintype "passive"))
      (node (ref "R19") (pin "1") (pinfunction "1_1") (pintype "passive"))
    )
    (net (code "42") (name "Net-(Q4-G)") (class "Default")
      (node (ref "Q4") (pin "1") (pinfunction "G_1") (pintype "passive"))
      (node (ref "R20") (pin "1") (pinfunction "1_1") (pintype "passive"))
    )
    (net (code "43") (name "Net-(Q5-G)") (class "Default")
      (node (ref "Q5") (pin "1") (pinfunction "G_1") (pintype "passive"))
      (node (ref "R21") (pin "1") (pinfunction "1_1") (pintype "passive"))
    )
    (net (code "44") (name "Net-(Q6-G)") (class "Default")
      (node (ref "Q6") (pin "1") (pinfunction "G_1") (pintype "passive"))
      (node (ref "R22") (pin "1") (pinfunction "1_1") (pintype "passive"))
    )
    (net (code "45") (name "unconnected-(J1-Pad6)") (class "Default")
      (node (ref "J1") (pin "6") (pinfunction "6_6") (pintype "passive+no_connect"))
    )
    (net (code "46") (name "unconnected-(U1-NC-Pad12)") (class "Default")
      (node (ref "U1") (pin "12") (pinfunction "NC_12") (pintype "passive+no_connect"))
    )
    (net (code "47") (name "unconnected-(U1-NC-Pad13)") (class "Default")
      (node (ref "U1") (pin "13") (pinfunction "NC_13") (pintype "passive+no_connect"))
    )
    (net (code "48") (name "unconnected-(U1-NC-Pad33)") (class "Default")
      (node (ref "U1") (pin "33") (pinfunction "NC_33") (pintype "passive+no_connect"))
    )
    (net (code "49") (name "unconnected-(U1-NC-Pad34)") (class "Default")
      (node (ref "U1") (pin "34") (pinfunction "NC_34") (pintype "passive+no_connect"))
    )
    (net (code "50") (name "unconnected-(U1-RA5-Pad24)") (class "Default")
      (node (ref "U1") (pin "24") (pinfunction "RA5_24") (pintype "bidirectional+no_connect"))
    )
    (net (code "51") (name "unconnected-(U1-RA6-Pad31)") (class "Default")
      (node (ref "U1") (pin "31") (pinfunction "RA6_31") (pintype "bidirectional+no_connect"))
    )
    (net (code "52") (name "unconnected-(U1-RA7-Pad30)") (class "Default")
      (node (ref "U1") (pin "30") (pinfunction "RA7_30") (pintype "bidirectional+no_connect"))
    )
    (net (code "53") (name "unconnected-(U1-RB0-Pad8)") (class "Default")
      (node (ref "U1") (pin "8") (pinfunction "RB0_8") (pintype "bidirectional+no_connect"))
    )
    (net (code "54") (name "unconnected-(U1-RB1-Pad9)") (class "Default")
      (node (ref "U1") (pin "9") (pinfunction "RB1_9") (pintype "bidirectional+no_connect"))
    )
    (net (code "55") (name "unconnected-(U1-RB2-Pad10)") (class "Default")
      (node (ref "U1") (pin "10") (pinfunction "RB2_10") (pintype "bidirectional+no_connect"))
    )
    (net (code "56") (name "unconnected-(U1-RB3-Pad11)") (class "Default")
      (node (ref "U1") (pin "11") (pinfunction "RB3_11") (pintype "bidirectional+no_connect"))
    )
    (net (code "57") (name "unconnected-(U1-RB4-Pad14)") (class "Default")
      (node (ref "U1") (pin "14") (pinfunction "RB4_14") (pintype "bidirectional+no_connect"))
    )
    (net (code "58") (name "unconnected-(U1-RB5-Pad15)") (class "Default")
      (node (ref "U1") (pin "15") (pinfunction "RB5_15") (pintype "bidirectional+no_connect"))
    )
    (net (code "59") (name "unconnected-(U1-RC0-Pad32)") (class "Default")
      (node (ref "U1") (pin "32") (pinfunction "RC0_32") (pintype "bidirectional+no_connect"))
    )
    (net (code "60") (name "unconnected-(U1-RC1-Pad35)") (class "Default")
      (node (ref "U1") (pin "35") (pinfunction "RC1_35") (pintype "bidirectional+no_connect"))
    )
    (net (code "61") (name "unconnected-(U1-RC2-Pad36)") (class "Default")
      (node (ref "U1") (pin "36") (pinfunction "RC2_36") (pintype "bidirectional+no_connect"))
    )
    (net (code "62") (name "unconnected-(U1-RC3-Pad37)") (class "Default")
      (node (ref "U1") (pin "37") (pinfunction "RC3_37") (pintype "bidirectional+no_connect"))
    )
    (net (code "63") (name "unconnected-(U1-RC4-Pad42)") (class "Default")
      (node (ref "U1") (pin "42") (pinfunction "RC4_42") (pintype "bidirectional+no_connect"))
    )
    (net (code "64") (name "unconnected-(U1-RC5-Pad43)") (class "Default")
      (node (ref "U1") (pin "43") (pinfunction "RC5_43") (pintype "bidirectional+no_connect"))
    )
    (net (code "65") (name "unconnected-(U1-RC7-Pad1)") (class "Default")
      (node (ref "U1") (pin "1") (pinfunction "RC7_1") (pintype "bidirectional+no_connect"))
    )
    (net (code "66") (name "unconnected-(U1-RE0-Pad25)") (class "Default")
      (node (ref "U1") (pin "25") (pinfunction "RE0_25") (pintype "bidirectional+no_connect"))
    )
    (net (code "67") (name "unconnected-(U1-RE1-Pad26)") (class "Default")
      (node (ref "U1") (pin "26") (pinfunction "RE1_26") (pintype "bidirectional+no_connect"))
    )
  )
)
